# Y1BVER2_0_2.net
KiCad netlist of a schematic drawn in Altium Designer
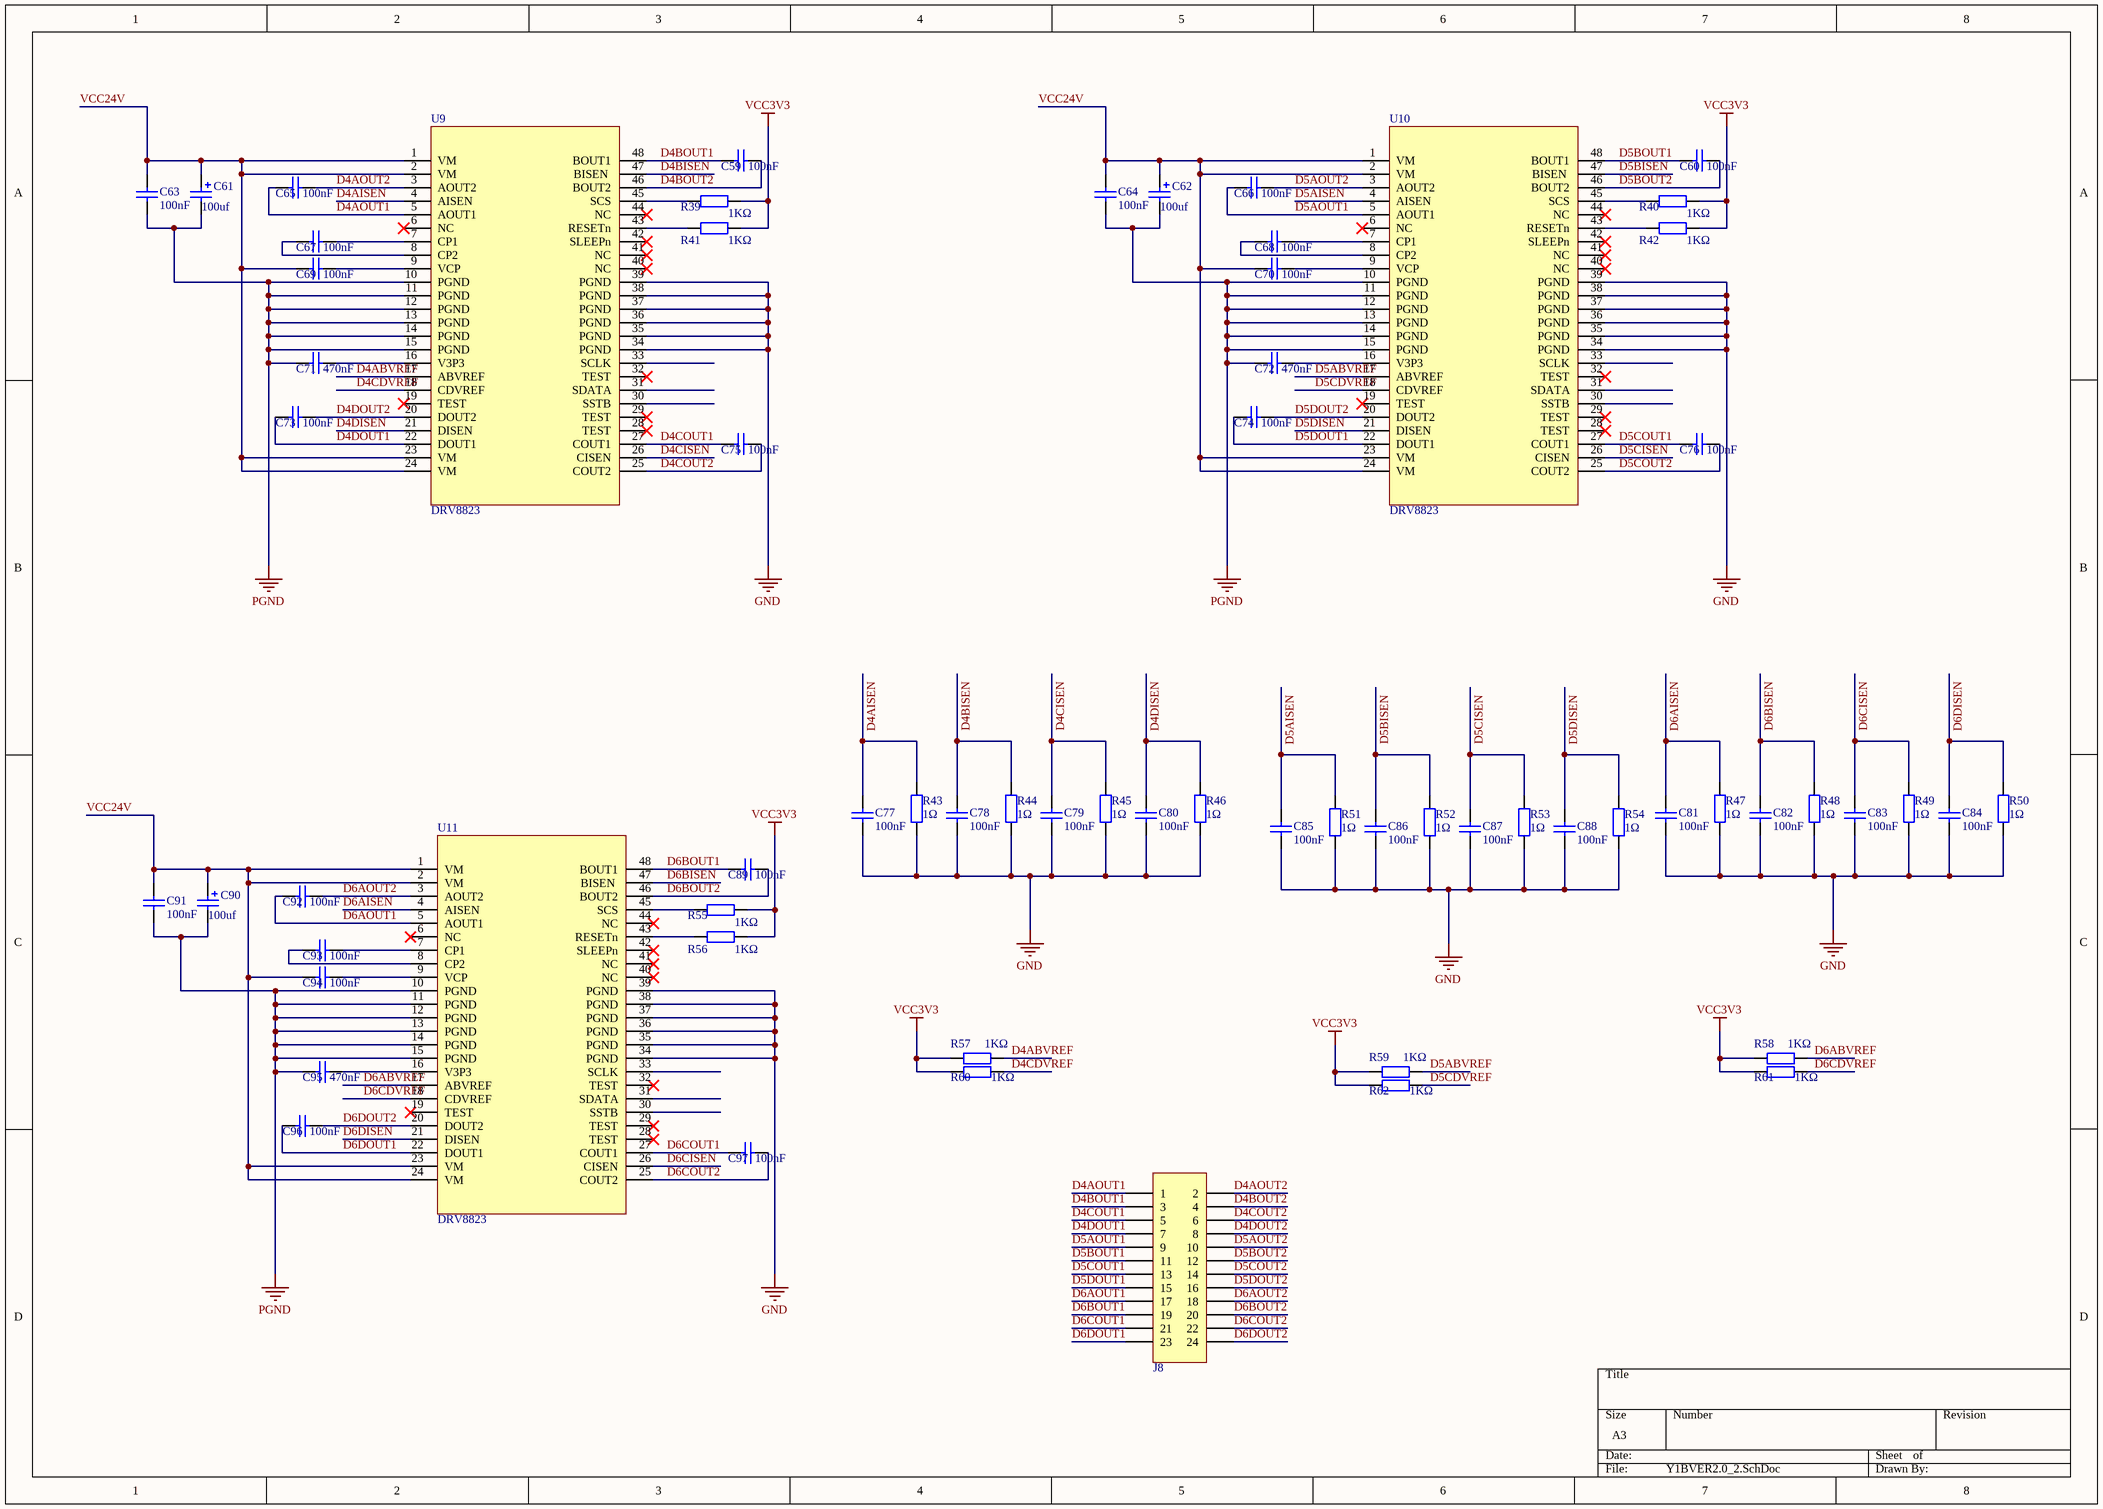
[diagram p0: Y1BVER2.0_2.SchDoc]

(export (version "E")
  (design (tool "Eeschema 10.0.6"))
  (components
    (comp (ref "C59")
      (value "100nF")
      (footprint "0603_C")
      (description "贴片电容")
      (libsource (lib "AD封装2018.9.19Miscellaneous Devices LC") (part "0603 100nF (104) 10% 50V"))
    )
    (comp (ref "C60")
      (value "100nF")
      (footprint "0603_C")
      (description "贴片电容")
      (libsource (lib "AD封装2018.9.19Miscellaneous Devices LC") (part "0603 100nF (104) 10% 50V"))
    )
    (comp (ref "C61") (value "100uf") (footprint "E_6.3*5.4") (libsource (lib "我的集成库") (part "C")))
    (comp (ref "C62") (value "100uf") (footprint "E_6.3*5.4") (libsource (lib "我的集成库") (part "C")))
    (comp (ref "C63")
      (value "100nF")
      (footprint "0603_C")
      (description "贴片电容")
      (libsource (lib "AD封装2018.9.19Miscellaneous Devices LC") (part "0603 100nF (104) 10% 50V"))
    )
    (comp (ref "C64")
      (value "100nF")
      (footprint "0603_C")
      (description "贴片电容")
      (libsource (lib "AD封装2018.9.19Miscellaneous Devices LC") (part "0603 100nF (104) 10% 50V"))
    )
    (comp (ref "C65")
      (value "100nF")
      (footprint "0603_C")
      (description "贴片电容")
      (libsource (lib "AD封装2018.9.19Miscellaneous Devices LC") (part "0603 100nF (104) 10% 50V"))
    )
    (comp (ref "C66")
      (value "100nF")
      (footprint "0603_C")
      (description "贴片电容")
      (libsource (lib "AD封装2018.9.19Miscellaneous Devices LC") (part "0603 100nF (104) 10% 50V"))
    )
    (comp (ref "C67")
      (value "100nF")
      (footprint "0603_C")
      (description "贴片电容")
      (libsource (lib "AD封装2018.9.19Miscellaneous Devices LC") (part "0603 100nF (104) 10% 50V"))
    )
    (comp (ref "C68")
      (value "100nF")
      (footprint "0603_C")
      (description "贴片电容")
      (libsource (lib "AD封装2018.9.19Miscellaneous Devices LC") (part "0603 100nF (104) 10% 50V"))
    )
    (comp (ref "C69")
      (value "100nF")
      (footprint "0603_C")
      (description "贴片电容")
      (libsource (lib "AD封装2018.9.19Miscellaneous Devices LC") (part "0603 100nF (104) 10% 50V"))
    )
    (comp (ref "C70")
      (value "100nF")
      (footprint "0603_C")
      (description "贴片电容")
      (libsource (lib "AD封装2018.9.19Miscellaneous Devices LC") (part "0603 100nF (104) 10% 50V"))
    )
    (comp (ref "C71")
      (value "470nF")
      (footprint "0603_C")
      (description "贴片电容")
      (libsource (lib "AD封装2018.9.19Miscellaneous Devices LC") (part "0603 470nF (474) 10% 25V"))
    )
    (comp (ref "C72")
      (value "470nF")
      (footprint "0603_C")
      (description "贴片电容")
      (libsource (lib "AD封装2018.9.19Miscellaneous Devices LC") (part "0603 470nF (474) 10% 25V"))
    )
    (comp (ref "C73")
      (value "100nF")
      (footprint "0603_C")
      (description "贴片电容")
      (libsource (lib "AD封装2018.9.19Miscellaneous Devices LC") (part "0603 100nF (104) 10% 50V"))
    )
    (comp (ref "C74")
      (value "100nF")
      (footprint "0603_C")
      (description "贴片电容")
      (libsource (lib "AD封装2018.9.19Miscellaneous Devices LC") (part "0603 100nF (104) 10% 50V"))
    )
    (comp (ref "C75")
      (value "100nF")
      (footprint "0603_C")
      (description "贴片电容")
      (libsource (lib "AD封装2018.9.19Miscellaneous Devices LC") (part "0603 100nF (104) 10% 50V"))
    )
    (comp (ref "C76")
      (value "100nF")
      (footprint "0603_C")
      (description "贴片电容")
      (libsource (lib "AD封装2018.9.19Miscellaneous Devices LC") (part "0603 100nF (104) 10% 50V"))
    )
    (comp (ref "C77")
      (value "100nF")
      (footprint "0603_C")
      (description "贴片电容")
      (libsource (lib "AD封装2018.9.19Miscellaneous Devices LC") (part "0603 100nF (104) 10% 50V"))
    )
    (comp (ref "C78")
      (value "100nF")
      (footprint "0603_C")
      (description "贴片电容")
      (libsource (lib "AD封装2018.9.19Miscellaneous Devices LC") (part "0603 100nF (104) 10% 50V"))
    )
    (comp (ref "C79")
      (value "100nF")
      (footprint "0603_C")
      (description "贴片电容")
      (libsource (lib "AD封装2018.9.19Miscellaneous Devices LC") (part "0603 100nF (104) 10% 50V"))
    )
    (comp (ref "C80")
      (value "100nF")
      (footprint "0603_C")
      (description "贴片电容")
      (libsource (lib "AD封装2018.9.19Miscellaneous Devices LC") (part "0603 100nF (104) 10% 50V"))
    )
    (comp (ref "C81")
      (value "100nF")
      (footprint "0603_C")
      (description "贴片电容")
      (libsource (lib "AD封装2018.9.19Miscellaneous Devices LC") (part "0603 100nF (104) 10% 50V"))
    )
    (comp (ref "C82")
      (value "100nF")
      (footprint "0603_C")
      (description "贴片电容")
      (libsource (lib "AD封装2018.9.19Miscellaneous Devices LC") (part "0603 100nF (104) 10% 50V"))
    )
    (comp (ref "C83")
      (value "100nF")
      (footprint "0603_C")
      (description "贴片电容")
      (libsource (lib "AD封装2018.9.19Miscellaneous Devices LC") (part "0603 100nF (104) 10% 50V"))
    )
    (comp (ref "C84")
      (value "100nF")
      (footprint "0603_C")
      (description "贴片电容")
      (libsource (lib "AD封装2018.9.19Miscellaneous Devices LC") (part "0603 100nF (104) 10% 50V"))
    )
    (comp (ref "C85")
      (value "100nF")
      (footprint "0603_C")
      (description "贴片电容")
      (libsource (lib "AD封装2018.9.19Miscellaneous Devices LC") (part "0603 100nF (104) 10% 50V"))
    )
    (comp (ref "C86")
      (value "100nF")
      (footprint "0603_C")
      (description "贴片电容")
      (libsource (lib "AD封装2018.9.19Miscellaneous Devices LC") (part "0603 100nF (104) 10% 50V"))
    )
    (comp (ref "C87")
      (value "100nF")
      (footprint "0603_C")
      (description "贴片电容")
      (libsource (lib "AD封装2018.9.19Miscellaneous Devices LC") (part "0603 100nF (104) 10% 50V"))
    )
    (comp (ref "C88")
      (value "100nF")
      (footprint "0603_C")
      (description "贴片电容")
      (libsource (lib "AD封装2018.9.19Miscellaneous Devices LC") (part "0603 100nF (104) 10% 50V"))
    )
    (comp (ref "C89")
      (value "100nF")
      (footprint "0603_C")
      (description "贴片电容")
      (libsource (lib "AD封装2018.9.19Miscellaneous Devices LC") (part "0603 100nF (104) 10% 50V"))
    )
    (comp (ref "C90") (value "100uf") (footprint "E_6.3*5.4") (libsource (lib "我的集成库") (part "C")))
    (comp (ref "C91")
      (value "100nF")
      (footprint "0603_C")
      (description "贴片电容")
      (libsource (lib "AD封装2018.9.19Miscellaneous Devices LC") (part "0603 100nF (104) 10% 50V"))
    )
    (comp (ref "C92")
      (value "100nF")
      (footprint "0603_C")
      (description "贴片电容")
      (libsource (lib "AD封装2018.9.19Miscellaneous Devices LC") (part "0603 100nF (104) 10% 50V"))
    )
    (comp (ref "C93")
      (value "100nF")
      (footprint "0603_C")
      (description "贴片电容")
      (libsource (lib "AD封装2018.9.19Miscellaneous Devices LC") (part "0603 100nF (104) 10% 50V"))
    )
    (comp (ref "C94")
      (value "100nF")
      (footprint "0603_C")
      (description "贴片电容")
      (libsource (lib "AD封装2018.9.19Miscellaneous Devices LC") (part "0603 100nF (104) 10% 50V"))
    )
    (comp (ref "C95")
      (value "470nF")
      (footprint "0603_C")
      (description "贴片电容")
      (libsource (lib "AD封装2018.9.19Miscellaneous Devices LC") (part "0603 470nF (474) 10% 25V"))
    )
    (comp (ref "C96")
      (value "100nF")
      (footprint "0603_C")
      (description "贴片电容")
      (libsource (lib "AD封装2018.9.19Miscellaneous Devices LC") (part "0603 100nF (104) 10% 50V"))
    )
    (comp (ref "C97")
      (value "100nF")
      (footprint "0603_C")
      (description "贴片电容")
      (libsource (lib "AD封装2018.9.19Miscellaneous Devices LC") (part "0603 100nF (104) 10% 50V"))
    )
    (comp (ref "J8")
      (value "header24p")
      (footprint "5557-2*12P")
      (libsource (lib "我的集成库") (part "header24p"))
    )
    (comp (ref "R39")
      (value "1KΩ")
      (footprint "0603_R")
      (description "贴片电阻")
      (libsource (lib "AD封装2018.9.19Miscellaneous Devices LC") (part "0603 1KΩ (1001) 1%"))
    )
    (comp (ref "R40")
      (value "1KΩ")
      (footprint "0603_R")
      (description "贴片电阻")
      (libsource (lib "AD封装2018.9.19Miscellaneous Devices LC") (part "0603 1KΩ (1001) 1%"))
    )
    (comp (ref "R41")
      (value "1KΩ")
      (footprint "0603_R")
      (description "贴片电阻")
      (libsource (lib "AD封装2018.9.19Miscellaneous Devices LC") (part "0603 1KΩ (1001) 1%"))
    )
    (comp (ref "R42")
      (value "1KΩ")
      (footprint "0603_R")
      (description "贴片电阻")
      (libsource (lib "AD封装2018.9.19Miscellaneous Devices LC") (part "0603 1KΩ (1001) 1%"))
    )
    (comp (ref "R43")
      (value "1Ω")
      (footprint "0603_R")
      (description "贴片电阻")
      (libsource (lib "AD封装2018.9.19Miscellaneous Devices LC") (part "0603 1Ω (1R00) 1%"))
    )
    (comp (ref "R44")
      (value "1Ω")
      (footprint "0603_R")
      (description "贴片电阻")
      (libsource (lib "AD封装2018.9.19Miscellaneous Devices LC") (part "0603 1Ω (1R00) 1%"))
    )
    (comp (ref "R45")
      (value "1Ω")
      (footprint "0603_R")
      (description "贴片电阻")
      (libsource (lib "AD封装2018.9.19Miscellaneous Devices LC") (part "0603 1Ω (1R00) 1%"))
    )
    (comp (ref "R46")
      (value "1Ω")
      (footprint "0603_R")
      (description "贴片电阻")
      (libsource (lib "AD封装2018.9.19Miscellaneous Devices LC") (part "0603 1Ω (1R00) 1%"))
    )
    (comp (ref "R47")
      (value "1Ω")
      (footprint "0603_R")
      (description "贴片电阻")
      (libsource (lib "AD封装2018.9.19Miscellaneous Devices LC") (part "0603 1Ω (1R00) 1%"))
    )
    (comp (ref "R48")
      (value "1Ω")
      (footprint "0603_R")
      (description "贴片电阻")
      (libsource (lib "AD封装2018.9.19Miscellaneous Devices LC") (part "0603 1Ω (1R00) 1%"))
    )
    (comp (ref "R49")
      (value "1Ω")
      (footprint "0603_R")
      (description "贴片电阻")
      (libsource (lib "AD封装2018.9.19Miscellaneous Devices LC") (part "0603 1Ω (1R00) 1%"))
    )
    (comp (ref "R50")
      (value "1Ω")
      (footprint "0603_R")
      (description "贴片电阻")
      (libsource (lib "AD封装2018.9.19Miscellaneous Devices LC") (part "0603 1Ω (1R00) 1%"))
    )
    (comp (ref "R51")
      (value "1Ω")
      (footprint "0603_R")
      (description "贴片电阻")
      (libsource (lib "AD封装2018.9.19Miscellaneous Devices LC") (part "0603 1Ω (1R00) 1%"))
    )
    (comp (ref "R52")
      (value "1Ω")
      (footprint "0603_R")
      (description "贴片电阻")
      (libsource (lib "AD封装2018.9.19Miscellaneous Devices LC") (part "0603 1Ω (1R00) 1%"))
    )
    (comp (ref "R53")
      (value "1Ω")
      (footprint "0603_R")
      (description "贴片电阻")
      (libsource (lib "AD封装2018.9.19Miscellaneous Devices LC") (part "0603 1Ω (1R00) 1%"))
    )
    (comp (ref "R54")
      (value "1Ω")
      (footprint "0603_R")
      (description "贴片电阻")
      (libsource (lib "AD封装2018.9.19Miscellaneous Devices LC") (part "0603 1Ω (1R00) 1%"))
    )
    (comp (ref "R55")
      (value "1KΩ")
      (footprint "0603_R")
      (description "贴片电阻")
      (libsource (lib "AD封装2018.9.19Miscellaneous Devices LC") (part "0603 1KΩ (1001) 1%"))
    )
    (comp (ref "R56")
      (value "1KΩ")
      (footprint "0603_R")
      (description "贴片电阻")
      (libsource (lib "AD封装2018.9.19Miscellaneous Devices LC") (part "0603 1KΩ (1001) 1%"))
    )
    (comp (ref "R57")
      (value "1KΩ")
      (footprint "0603_R")
      (description "贴片电阻")
      (libsource (lib "AD封装2018.9.19Miscellaneous Devices LC") (part "0603 1KΩ (1001) 1%"))
    )
    (comp (ref "R58")
      (value "1KΩ")
      (footprint "0603_R")
      (description "贴片电阻")
      (libsource (lib "AD封装2018.9.19Miscellaneous Devices LC") (part "0603 1KΩ (1001) 1%"))
    )
    (comp (ref "R59")
      (value "1KΩ")
      (footprint "0603_R")
      (description "贴片电阻")
      (libsource (lib "AD封装2018.9.19Miscellaneous Devices LC") (part "0603 1KΩ (1001) 1%"))
    )
    (comp (ref "R60")
      (value "1KΩ")
      (footprint "0603_R")
      (description "贴片电阻")
      (libsource (lib "AD封装2018.9.19Miscellaneous Devices LC") (part "0603 1KΩ (1001) 1%"))
    )
    (comp (ref "R61")
      (value "1KΩ")
      (footprint "0603_R")
      (description "贴片电阻")
      (libsource (lib "AD封装2018.9.19Miscellaneous Devices LC") (part "0603 1KΩ (1001) 1%"))
    )
    (comp (ref "R62")
      (value "1KΩ")
      (footprint "0603_R")
      (description "贴片电阻")
      (libsource (lib "AD封装2018.9.19Miscellaneous Devices LC") (part "0603 1KΩ (1001) 1%"))
    )
    (comp (ref "U9")
      (value "DRV8823")
      (footprint "HTSSOP-48")
      (description "4路BDC电机驱动")
      (libsource (lib "我的原理图库") (part "DRV8823"))
    )
    (comp (ref "U10")
      (value "DRV8823")
      (footprint "HTSSOP-48")
      (description "4路BDC电机驱动")
      (libsource (lib "我的原理图库") (part "DRV8823"))
    )
    (comp (ref "U11")
      (value "DRV8823")
      (footprint "HTSSOP-48")
      (description "4路BDC电机驱动")
      (libsource (lib "我的原理图库") (part "DRV8823"))
    )
  )
  (nets
    (net (code "1") (name "/D4ABVREF") (class "Default")
      (node (ref "R57") (pin "2") (pinfunction "2_2") (pintype "passive"))
      (node (ref "U9") (pin "17") (pinfunction "ABVREF_17") (pintype "passive"))
    )
    (net (code "2") (name "/D4AISEN") (class "Default")
      (node (ref "C77") (pin "2") (pinfunction "2_2") (pintype "passive"))
      (node (ref "R43") (pin "2") (pinfunction "2_2") (pintype "passive"))
      (node (ref "U9") (pin "4") (pinfunction "AISEN_4") (pintype "passive"))
    )
    (net (code "3") (name "/D4AOUT1") (class "Default")
      (node (ref "C65") (pin "1") (pinfunction "1_1") (pintype "passive"))
      (node (ref "J8") (pin "1") (pinfunction "1_1") (pintype "passive"))
      (node (ref "U9") (pin "5") (pinfunction "AOUT1_5") (pintype "passive"))
    )
    (net (code "4") (name "/D4AOUT2") (class "Default")
      (node (ref "C65") (pin "2") (pinfunction "2_2") (pintype "passive"))
      (node (ref "J8") (pin "2") (pinfunction "2_2") (pintype "passive"))
      (node (ref "U9") (pin "3") (pinfunction "AOUT2_3") (pintype "passive"))
    )
    (net (code "5") (name "/D4BISEN") (class "Default")
      (node (ref "C78") (pin "2") (pinfunction "2_2") (pintype "passive"))
      (node (ref "R44") (pin "2") (pinfunction "2_2") (pintype "passive"))
      (node (ref "U9") (pin "47") (pinfunction "BISEN_47") (pintype "passive"))
    )
    (net (code "6") (name "/D4BOUT1") (class "Default")
      (node (ref "C59") (pin "1") (pinfunction "1_1") (pintype "passive"))
      (node (ref "J8") (pin "3") (pinfunction "3_3") (pintype "passive"))
      (node (ref "U9") (pin "48") (pinfunction "BOUT1_48") (pintype "passive"))
    )
    (net (code "7") (name "/D4BOUT2") (class "Default")
      (node (ref "C59") (pin "2") (pinfunction "2_2") (pintype "passive"))
      (node (ref "J8") (pin "4") (pinfunction "4_4") (pintype "passive"))
      (node (ref "U9") (pin "46") (pinfunction "BOUT2_46") (pintype "passive"))
    )
    (net (code "8") (name "/D4CDVREF") (class "Default")
      (node (ref "R60") (pin "2") (pinfunction "2_2") (pintype "passive"))
      (node (ref "U9") (pin "18") (pinfunction "CDVREF_18") (pintype "passive"))
    )
    (net (code "9") (name "/D4CISEN") (class "Default")
      (node (ref "C79") (pin "2") (pinfunction "2_2") (pintype "passive"))
      (node (ref "R45") (pin "2") (pinfunction "2_2") (pintype "passive"))
      (node (ref "U9") (pin "26") (pinfunction "CISEN_26") (pintype "passive"))
    )
    (net (code "10") (name "/D4COUT1") (class "Default")
      (node (ref "C75") (pin "1") (pinfunction "1_1") (pintype "passive"))
      (node (ref "J8") (pin "5") (pinfunction "5_5") (pintype "passive"))
      (node (ref "U9") (pin "27") (pinfunction "COUT1_27") (pintype "passive"))
    )
    (net (code "11") (name "/D4COUT2") (class "Default")
      (node (ref "C75") (pin "2") (pinfunction "2_2") (pintype "passive"))
      (node (ref "J8") (pin "6") (pinfunction "6_6") (pintype "passive"))
      (node (ref "U9") (pin "25") (pinfunction "COUT2_25") (pintype "passive"))
    )
    (net (code "12") (name "/D4DISEN") (class "Default")
      (node (ref "C80") (pin "2") (pinfunction "2_2") (pintype "passive"))
      (node (ref "R46") (pin "2") (pinfunction "2_2") (pintype "passive"))
      (node (ref "U9") (pin "21") (pinfunction "DISEN_21") (pintype "passive"))
    )
    (net (code "13") (name "/D4DOUT1") (class "Default")
      (node (ref "C73") (pin "1") (pinfunction "1_1") (pintype "passive"))
      (node (ref "J8") (pin "7") (pinfunction "7_7") (pintype "passive"))
      (node (ref "U9") (pin "22") (pinfunction "DOUT1_22") (pintype "passive"))
    )
    (net (code "14") (name "/D4DOUT2") (class "Default")
      (node (ref "C73") (pin "2") (pinfunction "2_2") (pintype "passive"))
      (node (ref "J8") (pin "8") (pinfunction "8_8") (pintype "passive"))
      (node (ref "U9") (pin "20") (pinfunction "DOUT2_20") (pintype "passive"))
    )
    (net (code "15") (name "/D5ABVREF") (class "Default")
      (node (ref "R59") (pin "2") (pinfunction "2_2") (pintype "passive"))
      (node (ref "U10") (pin "17") (pinfunction "ABVREF_17") (pintype "passive"))
    )
    (net (code "16") (name "/D5AISEN") (class "Default")
      (node (ref "C85") (pin "2") (pinfunction "2_2") (pintype "passive"))
      (node (ref "R51") (pin "2") (pinfunction "2_2") (pintype "passive"))
      (node (ref "U10") (pin "4") (pinfunction "AISEN_4") (pintype "passive"))
    )
    (net (code "17") (name "/D5AOUT1") (class "Default")
      (node (ref "C66") (pin "1") (pinfunction "1_1") (pintype "passive"))
      (node (ref "J8") (pin "9") (pinfunction "9_9") (pintype "passive"))
      (node (ref "U10") (pin "5") (pinfunction "AOUT1_5") (pintype "passive"))
    )
    (net (code "18") (name "/D5AOUT2") (class "Default")
      (node (ref "C66") (pin "2") (pinfunction "2_2") (pintype "passive"))
      (node (ref "J8") (pin "10") (pinfunction "10_10") (pintype "passive"))
      (node (ref "U10") (pin "3") (pinfunction "AOUT2_3") (pintype "passive"))
    )
    (net (code "19") (name "/D5BISEN") (class "Default")
      (node (ref "C86") (pin "2") (pinfunction "2_2") (pintype "passive"))
      (node (ref "R52") (pin "2") (pinfunction "2_2") (pintype "passive"))
      (node (ref "U10") (pin "47") (pinfunction "BISEN_47") (pintype "passive"))
    )
    (net (code "20") (name "/D5BOUT1") (class "Default")
      (node (ref "C60") (pin "1") (pinfunction "1_1") (pintype "passive"))
      (node (ref "J8") (pin "11") (pinfunction "11_11") (pintype "passive"))
      (node (ref "U10") (pin "48") (pinfunction "BOUT1_48") (pintype "passive"))
    )
    (net (code "21") (name "/D5BOUT2") (class "Default")
      (node (ref "C60") (pin "2") (pinfunction "2_2") (pintype "passive"))
      (node (ref "J8") (pin "12") (pinfunction "12_12") (pintype "passive"))
      (node (ref "U10") (pin "46") (pinfunction "BOUT2_46") (pintype "passive"))
    )
    (net (code "22") (name "/D5CDVREF") (class "Default")
      (node (ref "R62") (pin "2") (pinfunction "2_2") (pintype "passive"))
      (node (ref "U10") (pin "18") (pinfunction "CDVREF_18") (pintype "passive"))
    )
    (net (code "23") (name "/D5CISEN") (class "Default")
      (node (ref "C87") (pin "2") (pinfunction "2_2") (pintype "passive"))
      (node (ref "R53") (pin "2") (pinfunction "2_2") (pintype "passive"))
      (node (ref "U10") (pin "26") (pinfunction "CISEN_26") (pintype "passive"))
    )
    (net (code "24") (name "/D5COUT1") (class "Default")
      (node (ref "C76") (pin "1") (pinfunction "1_1") (pintype "passive"))
      (node (ref "J8") (pin "13") (pinfunction "13_13") (pintype "passive"))
      (node (ref "U10") (pin "27") (pinfunction "COUT1_27") (pintype "passive"))
    )
    (net (code "25") (name "/D5COUT2") (class "Default")
      (node (ref "C76") (pin "2") (pinfunction "2_2") (pintype "passive"))
      (node (ref "J8") (pin "14") (pinfunction "14_14") (pintype "passive"))
      (node (ref "U10") (pin "25") (pinfunction "COUT2_25") (pintype "passive"))
    )
    (net (code "26") (name "/D5DISEN") (class "Default")
      (node (ref "C88") (pin "2") (pinfunction "2_2") (pintype "passive"))
      (node (ref "R54") (pin "2") (pinfunction "2_2") (pintype "passive"))
      (node (ref "U10") (pin "21") (pinfunction "DISEN_21") (pintype "passive"))
    )
    (net (code "27") (name "/D5DOUT1") (class "Default")
      (node (ref "C74") (pin "1") (pinfunction "1_1") (pintype "passive"))
      (node (ref "J8") (pin "15") (pinfunction "15_15") (pintype "passive"))
      (node (ref "U10") (pin "22") (pinfunction "DOUT1_22") (pintype "passive"))
    )
    (net (code "28") (name "/D5DOUT2") (class "Default")
      (node (ref "C74") (pin "2") (pinfunction "2_2") (pintype "passive"))
      (node (ref "J8") (pin "16") (pinfunction "16_16") (pintype "passive"))
      (node (ref "U10") (pin "20") (pinfunction "DOUT2_20") (pintype "passive"))
    )
    (net (code "29") (name "/D6ABVREF") (class "Default")
      (node (ref "R58") (pin "2") (pinfunction "2_2") (pintype "passive"))
      (node (ref "U11") (pin "17") (pinfunction "ABVREF_17") (pintype "passive"))
    )
    (net (code "30") (name "/D6AISEN") (class "Default")
      (node (ref "C81") (pin "2") (pinfunction "2_2") (pintype "passive"))
      (node (ref "R47") (pin "2") (pinfunction "2_2") (pintype "passive"))
      (node (ref "U11") (pin "4") (pinfunction "AISEN_4") (pintype "passive"))
    )
    (net (code "31") (name "/D6AOUT1") (class "Default")
      (node (ref "C92") (pin "1") (pinfunction "1_1") (pintype "passive"))
      (node (ref "J8") (pin "17") (pinfunction "17_17") (pintype "passive"))
      (node (ref "U11") (pin "5") (pinfunction "AOUT1_5") (pintype "passive"))
    )
    (net (code "32") (name "/D6AOUT2") (class "Default")
      (node (ref "C92") (pin "2") (pinfunction "2_2") (pintype "passive"))
      (node (ref "J8") (pin "18") (pinfunction "18_18") (pintype "passive"))
      (node (ref "U11") (pin "3") (pinfunction "AOUT2_3") (pintype "passive"))
    )
    (net (code "33") (name "/D6BISEN") (class "Default")
      (node (ref "C82") (pin "2") (pinfunction "2_2") (pintype "passive"))
      (node (ref "R48") (pin "2") (pinfunction "2_2") (pintype "passive"))
      (node (ref "U11") (pin "47") (pinfunction "BISEN_47") (pintype "passive"))
    )
    (net (code "34") (name "/D6BOUT1") (class "Default")
      (node (ref "C89") (pin "1") (pinfunction "1_1") (pintype "passive"))
      (node (ref "J8") (pin "19") (pinfunction "19_19") (pintype "passive"))
      (node (ref "U11") (pin "48") (pinfunction "BOUT1_48") (pintype "passive"))
    )
    (net (code "35") (name "/D6BOUT2") (class "Default")
      (node (ref "C89") (pin "2") (pinfunction "2_2") (pintype "passive"))
      (node (ref "J8") (pin "20") (pinfunction "20_20") (pintype "passive"))
      (node (ref "U11") (pin "46") (pinfunction "BOUT2_46") (pintype "passive"))
    )
    (net (code "36") (name "/D6CDVREF") (class "Default")
      (node (ref "R61") (pin "2") (pinfunction "2_2") (pintype "passive"))
      (node (ref "U11") (pin "18") (pinfunction "CDVREF_18") (pintype "passive"))
    )
    (net (code "37") (name "/D6CISEN") (class "Default")
      (node (ref "C83") (pin "2") (pinfunction "2_2") (pintype "passive"))
      (node (ref "R49") (pin "2") (pinfunction "2_2") (pintype "passive"))
      (node (ref "U11") (pin "26") (pinfunction "CISEN_26") (pintype "passive"))
    )
    (net (code "38") (name "/D6COUT1") (class "Default")
      (node (ref "C97") (pin "1") (pinfunction "1_1") (pintype "passive"))
      (node (ref "J8") (pin "21") (pinfunction "21_21") (pintype "passive"))
      (node (ref "U11") (pin "27") (pinfunction "COUT1_27") (pintype "passive"))
    )
    (net (code "39") (name "/D6COUT2") (class "Default")
      (node (ref "C97") (pin "2") (pinfunction "2_2") (pintype "passive"))
      (node (ref "J8") (pin "22") (pinfunction "22_22") (pintype "passive"))
      (node (ref "U11") (pin "25") (pinfunction "COUT2_25") (pintype "passive"))
    )
    (net (code "40") (name "/D6DISEN") (class "Default")
      (node (ref "C84") (pin "2") (pinfunction "2_2") (pintype "passive"))
      (node (ref "R50") (pin "2") (pinfunction "2_2") (pintype "passive"))
      (node (ref "U11") (pin "21") (pinfunction "DISEN_21") (pintype "passive"))
    )
    (net (code "41") (name "/D6DOUT1") (class "Default")
      (node (ref "C96") (pin "1") (pinfunction "1_1") (pintype "passive"))
      (node (ref "J8") (pin "23") (pinfunction "23_23") (pintype "passive"))
      (node (ref "U11") (pin "22") (pinfunction "DOUT1_22") (pintype "passive"))
    )
    (net (code "42") (name "/D6DOUT2") (class "Default")
      (node (ref "C96") (pin "2") (pinfunction "2_2") (pintype "passive"))
      (node (ref "J8") (pin "24") (pinfunction "24_24") (pintype "passive"))
      (node (ref "U11") (pin "20") (pinfunction "DOUT2_20") (pintype "passive"))
    )
    (net (code "43") (name "/VCC24V") (class "Default")
      (node (ref "C61") (pin "1") (pinfunction "1_1") (pintype "passive"))
      (node (ref "C62") (pin "1") (pinfunction "1_1") (pintype "passive"))
      (node (ref "C63") (pin "2") (pinfunction "2_2") (pintype "passive"))
      (node (ref "C64") (pin "2") (pinfunction "2_2") (pintype "passive"))
      (node (ref "C69") (pin "1") (pinfunction "1_1") (pintype "passive"))
      (node (ref "C70") (pin "1") (pinfunction "1_1") (pintype "passive"))
      (node (ref "C90") (pin "1") (pinfunction "1_1") (pintype "passive"))
      (node (ref "C91") (pin "2") (pinfunction "2_2") (pintype "passive"))
      (node (ref "C94") (pin "1") (pinfunction "1_1") (pintype "passive"))
      (node (ref "U10") (pin "1") (pinfunction "VM_1") (pintype "passive"))
      (node (ref "U10") (pin "2") (pinfunction "VM_2") (pintype "passive"))
      (node (ref "U10") (pin "23") (pinfunction "VM_23") (pintype "passive"))
      (node (ref "U10") (pin "24") (pinfunction "VM_24") (pintype "passive"))
      (node (ref "U11") (pin "1") (pinfunction "VM_1") (pintype "passive"))
      (node (ref "U11") (pin "2") (pinfunction "VM_2") (pintype "passive"))
      (node (ref "U11") (pin "23") (pinfunction "VM_23") (pintype "passive"))
      (node (ref "U11") (pin "24") (pinfunction "VM_24") (pintype "passive"))
      (node (ref "U9") (pin "1") (pinfunction "VM_1") (pintype "passive"))
      (node (ref "U9") (pin "2") (pinfunction "VM_2") (pintype "passive"))
      (node (ref "U9") (pin "23") (pinfunction "VM_23") (pintype "passive"))
      (node (ref "U9") (pin "24") (pinfunction "VM_24") (pintype "passive"))
    )
    (net (code "44") (name "GND") (class "Default")
      (node (ref "C77") (pin "1") (pinfunction "1_1") (pintype "passive"))
      (node (ref "C78") (pin "1") (pinfunction "1_1") (pintype "passive"))
      (node (ref "C79") (pin "1") (pinfunction "1_1") (pintype "passive"))
      (node (ref "C80") (pin "1") (pinfunction "1_1") (pintype "passive"))
      (node (ref "C81") (pin "1") (pinfunction "1_1") (pintype "passive"))
      (node (ref "C82") (pin "1") (pinfunction "1_1") (pintype "passive"))
      (node (ref "C83") (pin "1") (pinfunction "1_1") (pintype "passive"))
      (node (ref "C84") (pin "1") (pinfunction "1_1") (pintype "passive"))
      (node (ref "C85") (pin "1") (pinfunction "1_1") (pintype "passive"))
      (node (ref "C86") (pin "1") (pinfunction "1_1") (pintype "passive"))
      (node (ref "C87") (pin "1") (pinfunction "1_1") (pintype "passive"))
      (node (ref "C88") (pin "1") (pinfunction "1_1") (pintype "passive"))
      (node (ref "R43") (pin "1") (pinfunction "1_1") (pintype "passive"))
      (node (ref "R44") (pin "1") (pinfunction "1_1") (pintype "passive"))
      (node (ref "R45") (pin "1") (pinfunction "1_1") (pintype "passive"))
      (node (ref "R46") (pin "1") (pinfunction "1_1") (pintype "passive"))
      (node (ref "R47") (pin "1") (pinfunction "1_1") (pintype "passive"))
      (node (ref "R48") (pin "1") (pinfunction "1_1") (pintype "passive"))
      (node (ref "R49") (pin "1") (pinfunction "1_1") (pintype "passive"))
      (node (ref "R50") (pin "1") (pinfunction "1_1") (pintype "passive"))
      (node (ref "R51") (pin "1") (pinfunction "1_1") (pintype "passive"))
      (node (ref "R52") (pin "1") (pinfunction "1_1") (pintype "passive"))
      (node (ref "R53") (pin "1") (pinfunction "1_1") (pintype "passive"))
      (node (ref "R54") (pin "1") (pinfunction "1_1") (pintype "passive"))
      (node (ref "U10") (pin "34") (pinfunction "PGND_34") (pintype "passive"))
      (node (ref "U10") (pin "35") (pinfunction "PGND_35") (pintype "passive"))
      (node (ref "U10") (pin "36") (pinfunction "PGND_36") (pintype "passive"))
      (node (ref "U10") (pin "37") (pinfunction "PGND_37") (pintype "passive"))
      (node (ref "U10") (pin "38") (pinfunction "PGND_38") (pintype "passive"))
      (node (ref "U10") (pin "39") (pinfunction "PGND_39") (pintype "passive"))
      (node (ref "U11") (pin "34") (pinfunction "PGND_34") (pintype "passive"))
      (node (ref "U11") (pin "35") (pinfunction "PGND_35") (pintype "passive"))
      (node (ref "U11") (pin "36") (pinfunction "PGND_36") (pintype "passive"))
      (node (ref "U11") (pin "37") (pinfunction "PGND_37") (pintype "passive"))
      (node (ref "U11") (pin "38") (pinfunction "PGND_38") (pintype "passive"))
      (node (ref "U11") (pin "39") (pinfunction "PGND_39") (pintype "passive"))
      (node (ref "U9") (pin "34") (pinfunction "PGND_34") (pintype "passive"))
      (node (ref "U9") (pin "35") (pinfunction "PGND_35") (pintype "passive"))
      (node (ref "U9") (pin "36") (pinfunction "PGND_36") (pintype "passive"))
      (node (ref "U9") (pin "37") (pinfunction "PGND_37") (pintype "passive"))
      (node (ref "U9") (pin "38") (pinfunction "PGND_38") (pintype "passive"))
      (node (ref "U9") (pin "39") (pinfunction "PGND_39") (pintype "passive"))
    )
    (net (code "45") (name "Net-(U9-CP1)") (class "Default")
      (node (ref "C67") (pin "2") (pinfunction "2_2") (pintype "passive"))
      (node (ref "U9") (pin "7") (pinfunction "CP1_7") (pintype "passive"))
    )
    (net (code "46") (name "Net-(U9-CP2)") (class "Default")
      (node (ref "C67") (pin "1") (pinfunction "1_1") (pintype "passive"))
      (node (ref "U9") (pin "8") (pinfunction "CP2_8") (pintype "passive"))
    )
    (net (code "47") (name "Net-(U9-RESETn)") (class "Default")
      (node (ref "R41") (pin "1") (pinfunction "1_1") (pintype "passive"))
      (node (ref "U9") (pin "43") (pinfunction "RESETn_43") (pintype "passive"))
    )
    (net (code "48") (name "Net-(U9-SCS)") (class "Default")
      (node (ref "R39") (pin "1") (pinfunction "1_1") (pintype "passive"))
      (node (ref "U9") (pin "45") (pinfunction "SCS_45") (pintype "passive"))
    )
    (net (code "49") (name "Net-(U9-V3P3)") (class "Default")
      (node (ref "C71") (pin "2") (pinfunction "2_2") (pintype "passive"))
      (node (ref "U9") (pin "16") (pinfunction "V3P3_16") (pintype "passive"))
    )
    (net (code "50") (name "Net-(U9-VCP)") (class "Default")
      (node (ref "C69") (pin "2") (pinfunction "2_2") (pintype "passive"))
      (node (ref "U9") (pin "9") (pinfunction "VCP_9") (pintype "passive"))
    )
    (net (code "51") (name "Net-(U10-CP1)") (class "Default")
      (node (ref "C68") (pin "2") (pinfunction "2_2") (pintype "passive"))
      (node (ref "U10") (pin "7") (pinfunction "CP1_7") (pintype "passive"))
    )
    (net (code "52") (name "Net-(U10-CP2)") (class "Default")
      (node (ref "C68") (pin "1") (pinfunction "1_1") (pintype "passive"))
      (node (ref "U10") (pin "8") (pinfunction "CP2_8") (pintype "passive"))
    )
    (net (code "53") (name "Net-(U10-RESETn)") (class "Default")
      (node (ref "R42") (pin "1") (pinfunction "1_1") (pintype "passive"))
      (node (ref "U10") (pin "43") (pinfunction "RESETn_43") (pintype "passive"))
    )
    (net (code "54") (name "Net-(U10-SCS)") (class "Default")
      (node (ref "R40") (pin "1") (pinfunction "1_1") (pintype "passive"))
      (node (ref "U10") (pin "45") (pinfunction "SCS_45") (pintype "passive"))
    )
    (net (code "55") (name "Net-(U10-V3P3)") (class "Default")
      (node (ref "C72") (pin "2") (pinfunction "2_2") (pintype "passive"))
      (node (ref "U10") (pin "16") (pinfunction "V3P3_16") (pintype "passive"))
    )
    (net (code "56") (name "Net-(U10-VCP)") (class "Default")
      (node (ref "C70") (pin "2") (pinfunction "2_2") (pintype "passive"))
      (node (ref "U10") (pin "9") (pinfunction "VCP_9") (pintype "passive"))
    )
    (net (code "57") (name "Net-(U11-CP1)") (class "Default")
      (node (ref "C93") (pin "2") (pinfunction "2_2") (pintype "passive"))
      (node (ref "U11") (pin "7") (pinfunction "CP1_7") (pintype "passive"))
    )
    (net (code "58") (name "Net-(U11-CP2)") (class "Default")
      (node (ref "C93") (pin "1") (pinfunction "1_1") (pintype "passive"))
      (node (ref "U11") (pin "8") (pinfunction "CP2_8") (pintype "passive"))
    )
    (net (code "59") (name "Net-(U11-RESETn)") (class "Default")
      (node (ref "R56") (pin "1") (pinfunction "1_1") (pintype "passive"))
      (node (ref "U11") (pin "43") (pinfunction "RESETn_43") (pintype "passive"))
    )
    (net (code "60") (name "Net-(U11-SCS)") (class "Default")
      (node (ref "R55") (pin "1") (pinfunction "1_1") (pintype "passive"))
      (node (ref "U11") (pin "45") (pinfunction "SCS_45") (pintype "passive"))
    )
    (net (code "61") (name "Net-(U11-V3P3)") (class "Default")
      (node (ref "C95") (pin "2") (pinfunction "2_2") (pintype "passive"))
      (node (ref "U11") (pin "16") (pinfunction "V3P3_16") (pintype "passive"))
    )
    (net (code "62") (name "Net-(U11-VCP)") (class "Default")
      (node (ref "C94") (pin "2") (pinfunction "2_2") (pintype "passive"))
      (node (ref "U11") (pin "9") (pinfunction "VCP_9") (pintype "passive"))
    )
    (net (code "63") (name "PGND") (class "Default")
      (node (ref "C61") (pin "2") (pinfunction "2_2") (pintype "passive"))
      (node (ref "C62") (pin "2") (pinfunction "2_2") (pintype "passive"))
      (node (ref "C63") (pin "1") (pinfunction "1_1") (pintype "passive"))
      (node (ref "C64") (pin "1") (pinfunction "1_1") (pintype "passive"))
      (node (ref "C71") (pin "1") (pinfunction "1_1") (pintype "passive"))
      (node (ref "C72") (pin "1") (pinfunction "1_1") (pintype "passive"))
      (node (ref "C90") (pin "2") (pinfunction "2_2") (pintype "passive"))
      (node (ref "C91") (pin "1") (pinfunction "1_1") (pintype "passive"))
      (node (ref "C95") (pin "1") (pinfunction "1_1") (pintype "passive"))
      (node (ref "U10") (pin "10") (pinfunction "PGND_10") (pintype "passive"))
      (node (ref "U10") (pin "11") (pinfunction "PGND_11") (pintype "passive"))
      (node (ref "U10") (pin "12") (pinfunction "PGND_12") (pintype "passive"))
      (node (ref "U10") (pin "13") (pinfunction "PGND_13") (pintype "passive"))
      (node (ref "U10") (pin "14") (pinfunction "PGND_14") (pintype "passive"))
      (node (ref "U10") (pin "15") (pinfunction "PGND_15") (pintype "passive"))
      (node (ref "U11") (pin "10") (pinfunction "PGND_10") (pintype "passive"))
      (node (ref "U11") (pin "11") (pinfunction "PGND_11") (pintype "passive"))
      (node (ref "U11") (pin "12") (pinfunction "PGND_12") (pintype "passive"))
      (node (ref "U11") (pin "13") (pinfunction "PGND_13") (pintype "passive"))
      (node (ref "U11") (pin "14") (pinfunction "PGND_14") (pintype "passive"))
      (node (ref "U11") (pin "15") (pinfunction "PGND_15") (pintype "passive"))
      (node (ref "U9") (pin "10") (pinfunction "PGND_10") (pintype "passive"))
      (node (ref "U9") (pin "11") (pinfunction "PGND_11") (pintype "passive"))
      (node (ref "U9") (pin "12") (pinfunction "PGND_12") (pintype "passive"))
      (node (ref "U9") (pin "13") (pinfunction "PGND_13") (pintype "passive"))
      (node (ref "U9") (pin "14") (pinfunction "PGND_14") (pintype "passive"))
      (node (ref "U9") (pin "15") (pinfunction "PGND_15") (pintype "passive"))
    )
    (net (code "64") (name "VCC3V3") (class "Default")
      (node (ref "R39") (pin "2") (pinfunction "2_2") (pintype "passive"))
      (node (ref "R40") (pin "2") (pinfunction "2_2") (pintype "passive"))
      (node (ref "R41") (pin "2") (pinfunction "2_2") (pintype "passive"))
      (node (ref "R42") (pin "2") (pinfunction "2_2") (pintype "passive"))
      (node (ref "R55") (pin "2") (pinfunction "2_2") (pintype "passive"))
      (node (ref "R56") (pin "2") (pinfunction "2_2") (pintype "passive"))
      (node (ref "R57") (pin "1") (pinfunction "1_1") (pintype "passive"))
      (node (ref "R58") (pin "1") (pinfunction "1_1") (pintype "passive"))
      (node (ref "R59") (pin "1") (pinfunction "1_1") (pintype "passive"))
      (node (ref "R60") (pin "1") (pinfunction "1_1") (pintype "passive"))
      (node (ref "R61") (pin "1") (pinfunction "1_1") (pintype "passive"))
      (node (ref "R62") (pin "1") (pinfunction "1_1") (pintype "passive"))
    )
    (net (code "65") (name "unconnected-(U9-NC-Pad6)") (class "Default")
      (node (ref "U9") (pin "6") (pinfunction "NC_6") (pintype "passive+no_connect"))
    )
    (net (code "66") (name "unconnected-(U9-NC-Pad40)") (class "Default")
      (node (ref "U9") (pin "40") (pinfunction "NC_40") (pintype "passive+no_connect"))
    )
    (net (code "67") (name "unconnected-(U9-NC-Pad41)") (class "Default")
      (node (ref "U9") (pin "41") (pinfunction "NC_41") (pintype "passive+no_connect"))
    )
    (net (code "68") (name "unconnected-(U9-NC-Pad44)") (class "Default")
      (node (ref "U9") (pin "44") (pinfunction "NC_44") (pintype "passive+no_connect"))
    )
    (net (code "69") (name "unconnected-(U9-SCLK-Pad33)") (class "Default")
      (node (ref "U9") (pin "33") (pinfunction "SCLK_33") (pintype "passive"))
    )
    (net (code "70") (name "unconnected-(U9-SDATA-Pad31)") (class "Default")
      (node (ref "U9") (pin "31") (pinfunction "SDATA_31") (pintype "passive"))
    )
    (net (code "71") (name "unconnected-(U9-SLEEPn-Pad42)") (class "Default")
      (node (ref "U9") (pin "42") (pinfunction "SLEEPn_42") (pintype "passive+no_connect"))
    )
    (net (code "72") (name "unconnected-(U9-SSTB-Pad30)") (class "Default")
      (node (ref "U9") (pin "30") (pinfunction "SSTB_30") (pintype "passive"))
    )
    (net (code "73") (name "unconnected-(U9-TEST-Pad19)") (class "Default")
      (node (ref "U9") (pin "19") (pinfunction "TEST_19") (pintype "passive+no_connect"))
    )
    (net (code "74") (name "unconnected-(U9-TEST-Pad28)") (class "Default")
      (node (ref "U9") (pin "28") (pinfunction "TEST_28") (pintype "passive+no_connect"))
    )
    (net (code "75") (name "unconnected-(U9-TEST-Pad29)") (class "Default")
      (node (ref "U9") (pin "29") (pinfunction "TEST_29") (pintype "passive+no_connect"))
    )
    (net (code "76") (name "unconnected-(U9-TEST-Pad32)") (class "Default")
      (node (ref "U9") (pin "32") (pinfunction "TEST_32") (pintype "passive+no_connect"))
    )
    (net (code "77") (name "unconnected-(U10-NC-Pad6)") (class "Default")
      (node (ref "U10") (pin "6") (pinfunction "NC_6") (pintype "passive+no_connect"))
    )
    (net (code "78") (name "unconnected-(U10-NC-Pad40)") (class "Default")
      (node (ref "U10") (pin "40") (pinfunction "NC_40") (pintype "passive+no_connect"))
    )
    (net (code "79") (name "unconnected-(U10-NC-Pad41)") (class "Default")
      (node (ref "U10") (pin "41") (pinfunction "NC_41") (pintype "passive+no_connect"))
    )
    (net (code "80") (name "unconnected-(U10-NC-Pad44)") (class "Default")
      (node (ref "U10") (pin "44") (pinfunction "NC_44") (pintype "passive+no_connect"))
    )
    (net (code "81") (name "unconnected-(U10-SCLK-Pad33)") (class "Default")
      (node (ref "U10") (pin "33") (pinfunction "SCLK_33") (pintype "passive"))
    )
    (net (code "82") (name "unconnected-(U10-SDATA-Pad31)") (class "Default")
      (node (ref "U10") (pin "31") (pinfunction "SDATA_31") (pintype "passive"))
    )
    (net (code "83") (name "unconnected-(U10-SLEEPn-Pad42)") (class "Default")
      (node (ref "U10") (pin "42") (pinfunction "SLEEPn_42") (pintype "passive+no_connect"))
    )
    (net (code "84") (name "unconnected-(U10-SSTB-Pad30)") (class "Default")
      (node (ref "U10") (pin "30") (pinfunction "SSTB_30") (pintype "passive"))
    )
    (net (code "85") (name "unconnected-(U10-TEST-Pad19)") (class "Default")
      (node (ref "U10") (pin "19") (pinfunction "TEST_19") (pintype "passive+no_connect"))
    )
    (net (code "86") (name "unconnected-(U10-TEST-Pad28)") (class "Default")
      (node (ref "U10") (pin "28") (pinfunction "TEST_28") (pintype "passive+no_connect"))
    )
    (net (code "87") (name "unconnected-(U10-TEST-Pad29)") (class "Default")
      (node (ref "U10") (pin "29") (pinfunction "TEST_29") (pintype "passive+no_connect"))
    )
    (net (code "88") (name "unconnected-(U10-TEST-Pad32)") (class "Default")
      (node (ref "U10") (pin "32") (pinfunction "TEST_32") (pintype "passive+no_connect"))
    )
    (net (code "89") (name "unconnected-(U11-NC-Pad6)") (class "Default")
      (node (ref "U11") (pin "6") (pinfunction "NC_6") (pintype "passive+no_connect"))
    )
    (net (code "90") (name "unconnected-(U11-NC-Pad40)") (class "Default")
      (node (ref "U11") (pin "40") (pinfunction "NC_40") (pintype "passive+no_connect"))
    )
    (net (code "91") (name "unconnected-(U11-NC-Pad41)") (class "Default")
      (node (ref "U11") (pin "41") (pinfunction "NC_41") (pintype "passive+no_connect"))
    )
    (net (code "92") (name "unconnected-(U11-NC-Pad44)") (class "Default")
      (node (ref "U11") (pin "44") (pinfunction "NC_44") (pintype "passive+no_connect"))
    )
    (net (code "93") (name "unconnected-(U11-SCLK-Pad33)") (class "Default")
      (node (ref "U11") (pin "33") (pinfunction "SCLK_33") (pintype "passive"))
    )
    (net (code "94") (name "unconnected-(U11-SDATA-Pad31)") (class "Default")
      (node (ref "U11") (pin "31") (pinfunction "SDATA_31") (pintype "passive"))
    )
    (net (code "95") (name "unconnected-(U11-SLEEPn-Pad42)") (class "Default")
      (node (ref "U11") (pin "42") (pinfunction "SLEEPn_42") (pintype "passive+no_connect"))
    )
    (net (code "96") (name "unconnected-(U11-SSTB-Pad30)") (class "Default")
      (node (ref "U11") (pin "30") (pinfunction "SSTB_30") (pintype "passive"))
    )
    (net (code "97") (name "unconnected-(U11-TEST-Pad19)") (class "Default")
      (node (ref "U11") (pin "19") (pinfunction "TEST_19") (pintype "passive+no_connect"))
    )
    (net (code "98") (name "unconnected-(U11-TEST-Pad28)") (class "Default")
      (node (ref "U11") (pin "28") (pinfunction "TEST_28") (pintype "passive+no_connect"))
    )
    (net (code "99") (name "unconnected-(U11-TEST-Pad29)") (class "Default")
      (node (ref "U11") (pin "29") (pinfunction "TEST_29") (pintype "passive+no_connect"))
    )
    (net (code "100") (name "unconnected-(U11-TEST-Pad32)") (class "Default")
      (node (ref "U11") (pin "32") (pinfunction "TEST_32") (pintype "passive+no_connect"))
    )
  )
)
